# TMotor_Rev2.net
KiCad netlist of a schematic drawn in EAGLE
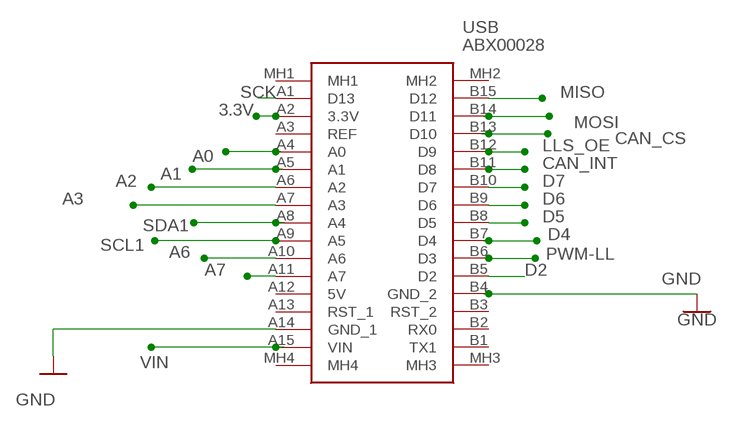
[diagram p0: schematic, sheet 1]
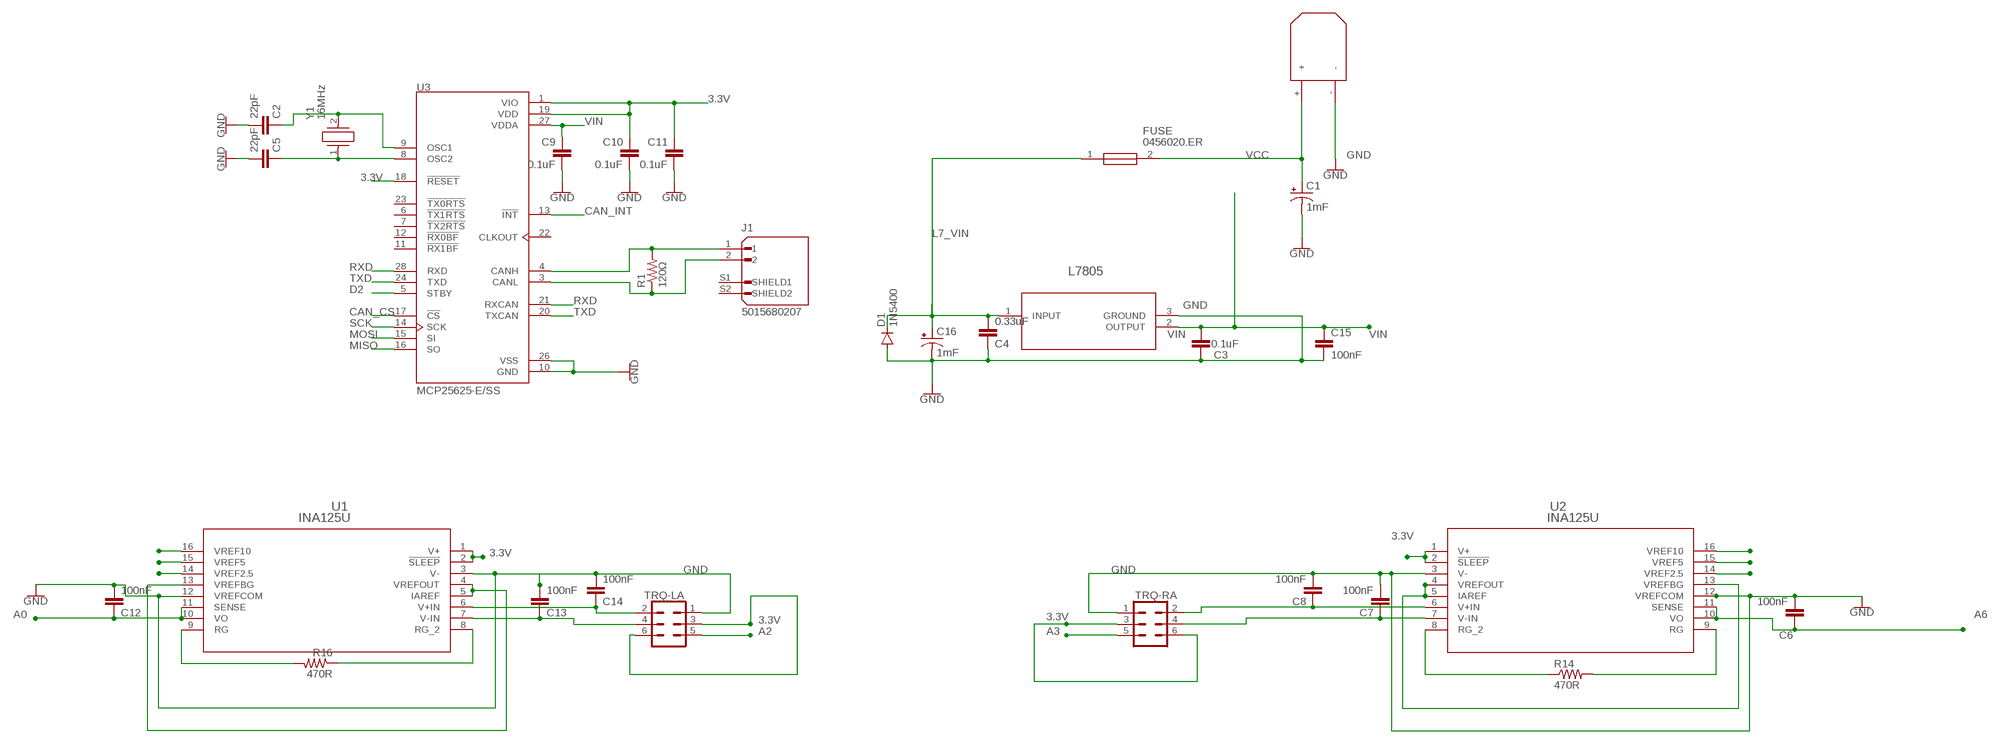
[diagram p1: schematic, sheet 2]
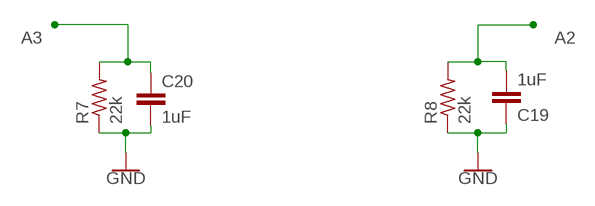
[diagram p2: schematic, sheet 3]

(export (version "E")
  (design (tool "Eeschema 10.0.6"))
  (components
    (comp (ref "C19")
      (value "1uF")
      (footprint "eagle-import:C050-024X044")
      (libsource (lib "eagle-import") (part "C-EU050-024X044"))
    )
    (comp (ref "C20")
      (value "1uF")
      (footprint "eagle-import:C050-024X044")
      (libsource (lib "eagle-import") (part "C-EU050-024X044"))
    )
    (comp (ref "R7")
      (value "22k")
      (footprint "eagle-import:0207_10")
      (libsource (lib "eagle-import") (part "resistor_348_R-US_0207/10"))
    )
    (comp (ref "R8")
      (value "22k")
      (footprint "eagle-import:0207_10")
      (libsource (lib "eagle-import") (part "resistor_348_R-US_0207/10"))
    )
    (comp (ref "USB")
      (value "ABX00028")
      (footprint "eagle-import:ABX00028")
      (fields (field (name "MOUSER_PART_NUMBER") "782-ABX00028"))
      (libsource (lib "eagle-import") (part "ABX00028"))
    )
    (comp (ref "C1")
      (value "1mF")
      (footprint "eagle-import:E5-10,5")
      (libsource (lib "eagle-import") (part "CPOL-USE5-10.5"))
    )
    (comp (ref "C2")
      (value "22pF")
      (footprint "eagle-import:C050-024X044")
      (libsource (lib "eagle-import") (part "C-EU050-024X044"))
    )
    (comp (ref "C3")
      (value "0.1uF")
      (footprint "eagle-import:C050-024X044")
      (libsource (lib "eagle-import") (part "C-EU050-024X044"))
    )
    (comp (ref "C4")
      (value "0.33uF")
      (footprint "eagle-import:C050-024X044")
      (libsource (lib "eagle-import") (part "C-EU050-024X044"))
    )
    (comp (ref "C5")
      (value "22pF")
      (footprint "eagle-import:C050-024X044")
      (libsource (lib "eagle-import") (part "C-EU050-024X044"))
    )
    (comp (ref "C6")
      (value "100nF")
      (footprint "eagle-import:C050-024X044")
      (libsource (lib "eagle-import") (part "C-EU050-024X044"))
    )
    (comp (ref "C7")
      (value "100nF")
      (footprint "eagle-import:C050-024X044")
      (libsource (lib "eagle-import") (part "C-EU050-024X044"))
    )
    (comp (ref "C8")
      (value "100nF")
      (footprint "eagle-import:C050-024X044")
      (libsource (lib "eagle-import") (part "C-EU050-024X044"))
    )
    (comp (ref "C9")
      (value "0.1uF")
      (footprint "eagle-import:C050-024X044")
      (libsource (lib "eagle-import") (part "C-EU050-024X044"))
    )
    (comp (ref "C10")
      (value "0.1uF")
      (footprint "eagle-import:C050-024X044")
      (libsource (lib "eagle-import") (part "C-EU050-024X044"))
    )
    (comp (ref "C11")
      (value "0.1uF")
      (footprint "eagle-import:C050-024X044")
      (libsource (lib "eagle-import") (part "C-EU050-024X044"))
    )
    (comp (ref "C12")
      (value "100nF")
      (footprint "eagle-import:C050-024X044")
      (libsource (lib "eagle-import") (part "C-EU050-024X044"))
    )
    (comp (ref "C13")
      (value "100nF")
      (footprint "eagle-import:C050-024X044")
      (libsource (lib "eagle-import") (part "C-EU050-024X044"))
    )
    (comp (ref "C14")
      (value "100nF")
      (footprint "eagle-import:C050-024X044")
      (libsource (lib "eagle-import") (part "C-EU050-024X044"))
    )
    (comp (ref "C15")
      (value "100nF")
      (footprint "eagle-import:C050-024X044")
      (libsource (lib "eagle-import") (part "C-EU050-024X044"))
    )
    (comp (ref "C16")
      (value "1mF")
      (footprint "eagle-import:E5-10,5")
      (libsource (lib "eagle-import") (part "CPOL-USE5-10.5"))
    )
    (comp (ref "D1")
      (value "1N5400")
      (footprint "eagle-import:DO201-15")
      (libsource (lib "eagle-import") (part "1N5400"))
    )
    (comp (ref "FUSE")
      (value "0456020.ER")
      (footprint "eagle-import:FUSC10131X312N")
      (fields (field (name "MOUSER_PART_NUMBER") "576-0456020.ER"))
      (libsource (lib "eagle-import") (part "0456020.ER"))
    )
    (comp (ref "J1")
      (value "5015680207")
      (footprint "eagle-import:MOLEX_5015680207")
      (fields (field (name "MANUFACTURER") "Molex"))
      (libsource (lib "eagle-import") (part "5015680207"))
    )
    (comp (ref "L7805")
      (value "L7805CDT-TR")
      (footprint "eagle-import:DPAK_STM")
      (libsource (lib "eagle-import") (part "L7805CDT-TR"))
    )
    (comp (ref "R1")
      (value "120Ω")
      (footprint "eagle-import:0207_10")
      (libsource (lib "eagle-import") (part "R-US_0207/10"))
    )
    (comp (ref "R14")
      (value "470R")
      (footprint "eagle-import:0207_10")
      (libsource (lib "eagle-import") (part "R-US_0207/10"))
    )
    (comp (ref "R16")
      (value "470R")
      (footprint "eagle-import:0207_10")
      (libsource (lib "eagle-import") (part "R-US_0207/10"))
    )
    (comp (ref "TRQ-LA")
      (value "CONN_03X2SHROUD")
      (footprint "eagle-import:2X3-SHROUDED")
      (libsource (lib "eagle-import") (part "CONN_03X2SHROUD"))
    )
    (comp (ref "TRQ-RA")
      (value "CONN_03X2SHROUD")
      (footprint "eagle-import:2X3-SHROUDED")
      (libsource (lib "eagle-import") (part "CONN_03X2SHROUD"))
    )
    (comp (ref "U$9")
      (value "XT30")
      (footprint "eagle-import:XT30_HORIZONTAL")
      (libsource (lib "eagle-import") (part "XT30"))
    )
    (comp (ref "U1")
      (value "INA125U")
      (footprint "eagle-import:D16")
      (fields (field (name "GENERIC_PART_NUMBER") "INA125") (field (name "MANUFACTURER") "Texas Instruments"))
      (libsource (lib "eagle-import") (part "INA125U"))
    )
    (comp (ref "U2")
      (value "INA125U")
      (footprint "eagle-import:D16")
      (fields (field (name "GENERIC_PART_NUMBER") "INA125") (field (name "MANUFACTURER") "Texas Instruments"))
      (libsource (lib "eagle-import") (part "INA125U"))
    )
    (comp (ref "U3")
      (value "MCP25625-E/SS")
      (footprint "eagle-import:SOP65P780X200-28N")
      (fields (field (name "MF") "Microchip Technology"))
      (libsource (lib "eagle-import") (part "MCP25625-E/SS"))
    )
    (comp (ref "Y1")
      (value "16MHz")
      (footprint "eagle-import:IQD-HC-49-4H")
      (fields (field (name "MANUFACTURER_PART_NUMBER") "4.91520MHz HC49/4H 30/50/-40+85C/30pF"))
      (libsource (lib "eagle-import") (part "4.91520MHZ_HC49_4H_30_50_-40+8"))
    )
  )
  (nets
    (net (code "1") (name "3.3V") (class "Default")
      (node (ref "C10") (pin "1") (pinfunction "1_1") (pintype "passive"))
      (node (ref "C11") (pin "1") (pinfunction "1_1") (pintype "passive"))
      (node (ref "TRQ-LA") (pin "3") (pinfunction "3_3") (pintype "bidirectional"))
      (node (ref "TRQ-LA") (pin "6") (pinfunction "6_6") (pintype "bidirectional"))
      (node (ref "TRQ-RA") (pin "3") (pinfunction "3_3") (pintype "bidirectional"))
      (node (ref "TRQ-RA") (pin "6") (pinfunction "6_6") (pintype "bidirectional"))
      (node (ref "U1") (pin "1") (pinfunction "V+_1") (pintype "power_in"))
      (node (ref "U1") (pin "2") (pinfunction "~{SLEEP}_2") (pintype "passive"))
      (node (ref "U2") (pin "1") (pinfunction "V+_1") (pintype "power_in"))
      (node (ref "U2") (pin "2") (pinfunction "~{SLEEP}_2") (pintype "passive"))
      (node (ref "U3") (pin "1") (pinfunction "VIO_1") (pintype "power_in"))
      (node (ref "U3") (pin "18") (pinfunction "~{RESET}_18") (pintype "input"))
      (node (ref "U3") (pin "19") (pinfunction "VDD_19") (pintype "power_in"))
      (node (ref "USB") (pin "A2") (pinfunction "3.3V_A2") (pintype "bidirectional"))
    )
    (net (code "2") (name "A0") (class "Default")
      (node (ref "C12") (pin "1") (pinfunction "1_1") (pintype "passive"))
      (node (ref "U1") (pin "10") (pinfunction "VO_10") (pintype "output"))
      (node (ref "U1") (pin "11") (pinfunction "SENSE_11") (pintype "passive"))
      (node (ref "USB") (pin "A4") (pinfunction "A0_A4") (pintype "bidirectional"))
    )
    (net (code "3") (name "A1") (class "Default")
      (node (ref "USB") (pin "A5") (pinfunction "A1_A5") (pintype "bidirectional"))
    )
    (net (code "4") (name "A2") (class "Default")
      (node (ref "C19") (pin "2") (pinfunction "2_2") (pintype "passive"))
      (node (ref "R8") (pin "2") (pinfunction "2_2") (pintype "passive"))
      (node (ref "TRQ-LA") (pin "5") (pinfunction "5_5") (pintype "bidirectional"))
      (node (ref "USB") (pin "A6") (pinfunction "A2_A6") (pintype "bidirectional"))
    )
    (net (code "5") (name "A3") (class "Default")
      (node (ref "C20") (pin "1") (pinfunction "1_1") (pintype "passive"))
      (node (ref "R7") (pin "2") (pinfunction "2_2") (pintype "passive"))
      (node (ref "TRQ-RA") (pin "5") (pinfunction "5_5") (pintype "bidirectional"))
      (node (ref "USB") (pin "A7") (pinfunction "A3_A7") (pintype "bidirectional"))
    )
    (net (code "6") (name "A6") (class "Default")
      (node (ref "C6") (pin "1") (pinfunction "1_1") (pintype "passive"))
      (node (ref "U2") (pin "10") (pinfunction "VO_10") (pintype "output"))
      (node (ref "U2") (pin "11") (pinfunction "SENSE_11") (pintype "passive"))
      (node (ref "USB") (pin "A10") (pinfunction "A6_A10") (pintype "bidirectional"))
    )
    (net (code "7") (name "A7") (class "Default")
      (node (ref "USB") (pin "A11") (pinfunction "A7_A11") (pintype "bidirectional"))
    )
    (net (code "8") (name "CAN_CS") (class "Default")
      (node (ref "U3") (pin "17") (pinfunction "~{CS}_17") (pintype "input"))
      (node (ref "USB") (pin "B13") (pinfunction "D10_B13") (pintype "bidirectional"))
    )
    (net (code "9") (name "CAN_INT") (class "Default")
      (node (ref "U3") (pin "13") (pinfunction "~{INT}_13") (pintype "output"))
      (node (ref "USB") (pin "B11") (pinfunction "D8_B11") (pintype "bidirectional"))
    )
    (net (code "10") (name "D2") (class "Default")
      (node (ref "U3") (pin "5") (pinfunction "STBY_5") (pintype "input"))
      (node (ref "USB") (pin "B5") (pinfunction "D2_B5") (pintype "bidirectional"))
    )
    (net (code "11") (name "D4") (class "Default")
      (node (ref "USB") (pin "B7") (pinfunction "D4_B7") (pintype "bidirectional"))
    )
    (net (code "12") (name "D5") (class "Default")
      (node (ref "USB") (pin "B8") (pinfunction "D5_B8") (pintype "bidirectional"))
    )
    (net (code "13") (name "D6") (class "Default")
      (node (ref "USB") (pin "B9") (pinfunction "D6_B9") (pintype "bidirectional"))
    )
    (net (code "14") (name "D7") (class "Default")
      (node (ref "USB") (pin "B10") (pinfunction "D7_B10") (pintype "bidirectional"))
    )
    (net (code "15") (name "GND") (class "Default")
      (node (ref "C1") (pin "-") (pinfunction "-_-") (pintype "passive"))
      (node (ref "C10") (pin "2") (pinfunction "2_2") (pintype "passive"))
      (node (ref "C11") (pin "2") (pinfunction "2_2") (pintype "passive"))
      (node (ref "C12") (pin "2") (pinfunction "2_2") (pintype "passive"))
      (node (ref "C13") (pin "2") (pinfunction "2_2") (pintype "passive"))
      (node (ref "C14") (pin "2") (pinfunction "2_2") (pintype "passive"))
      (node (ref "C15") (pin "2") (pinfunction "2_2") (pintype "passive"))
      (node (ref "C16") (pin "-") (pinfunction "-_-") (pintype "passive"))
      (node (ref "C19") (pin "1") (pinfunction "1_1") (pintype "passive"))
      (node (ref "C2") (pin "2") (pinfunction "2_2") (pintype "passive"))
      (node (ref "C20") (pin "2") (pinfunction "2_2") (pintype "passive"))
      (node (ref "C3") (pin "1") (pinfunction "1_1") (pintype "passive"))
      (node (ref "C4") (pin "1") (pinfunction "1_1") (pintype "passive"))
      (node (ref "C5") (pin "2") (pinfunction "2_2") (pintype "passive"))
      (node (ref "C6") (pin "2") (pinfunction "2_2") (pintype "passive"))
      (node (ref "C7") (pin "2") (pinfunction "2_2") (pintype "passive"))
      (node (ref "C8") (pin "2") (pinfunction "2_2") (pintype "passive"))
      (node (ref "C9") (pin "2") (pinfunction "2_2") (pintype "passive"))
      (node (ref "D1") (pin "A") (pinfunction "A_A") (pintype "passive"))
      (node (ref "L7805") (pin "3") (pinfunction "GROUND_3") (pintype "passive"))
      (node (ref "R7") (pin "1") (pinfunction "1_1") (pintype "passive"))
      (node (ref "R8") (pin "1") (pinfunction "1_1") (pintype "passive"))
      (node (ref "TRQ-LA") (pin "1") (pinfunction "1_1") (pintype "bidirectional"))
      (node (ref "TRQ-RA") (pin "1") (pinfunction "1_1") (pintype "bidirectional"))
      (node (ref "U$9") (pin "-") (pinfunction "-_-") (pintype "bidirectional"))
      (node (ref "U1") (pin "12") (pinfunction "VREFCOM_12") (pintype "power_in"))
      (node (ref "U1") (pin "3") (pinfunction "V-_3") (pintype "power_in"))
      (node (ref "U2") (pin "12") (pinfunction "VREFCOM_12") (pintype "power_in"))
      (node (ref "U2") (pin "3") (pinfunction "V-_3") (pintype "power_in"))
      (node (ref "U3") (pin "10") (pinfunction "GND_10") (pintype "power_in"))
      (node (ref "U3") (pin "26") (pinfunction "VSS_26") (pintype "power_in"))
      (node (ref "USB") (pin "A14") (pinfunction "GND_1_A14") (pintype "bidirectional"))
      (node (ref "USB") (pin "B4") (pinfunction "GND_2_B4") (pintype "bidirectional"))
    )
    (net (code "16") (name "L7_VIN") (class "Default")
      (node (ref "C16") (pin "+") (pinfunction "+_+") (pintype "passive"))
      (node (ref "C4") (pin "2") (pinfunction "2_2") (pintype "passive"))
      (node (ref "D1") (pin "C") (pinfunction "C_C") (pintype "passive"))
      (node (ref "FUSE") (pin "1") (pinfunction "1_1") (pintype "bidirectional"))
      (node (ref "L7805") (pin "1") (pinfunction "INPUT_1") (pintype "input"))
    )
    (net (code "17") (name "LLS_OE") (class "Default")
      (node (ref "USB") (pin "B12") (pinfunction "D9_B12") (pintype "bidirectional"))
    )
    (net (code "18") (name "MISO") (class "Default")
      (node (ref "U3") (pin "16") (pinfunction "SO_16") (pintype "output"))
      (node (ref "USB") (pin "B15") (pinfunction "D12_B15") (pintype "bidirectional"))
    )
    (net (code "19") (name "MOSI") (class "Default")
      (node (ref "U3") (pin "15") (pinfunction "SI_15") (pintype "input"))
      (node (ref "USB") (pin "B14") (pinfunction "D11_B14") (pintype "bidirectional"))
    )
    (net (code "20") (name "Net-(U1-IAREF)") (class "Default")
      (node (ref "U1") (pin "13") (pinfunction "VREFBG_13") (pintype "power_in"))
      (node (ref "U1") (pin "4") (pinfunction "VREFOUT_4") (pintype "output"))
      (node (ref "U1") (pin "5") (pinfunction "IAREF_5") (pintype "passive"))
    )
    (net (code "21") (name "Net-(U1-RG)") (class "Default")
      (node (ref "R16") (pin "2") (pinfunction "2_2") (pintype "passive"))
      (node (ref "U1") (pin "9") (pinfunction "RG_9") (pintype "passive"))
    )
    (net (code "22") (name "Net-(U1-RG_2)") (class "Default")
      (node (ref "R16") (pin "1") (pinfunction "1_1") (pintype "passive"))
      (node (ref "U1") (pin "8") (pinfunction "RG_2_8") (pintype "passive"))
    )
    (net (code "23") (name "Net-(U1-V+IN)") (class "Default")
      (node (ref "C14") (pin "1") (pinfunction "1_1") (pintype "passive"))
      (node (ref "TRQ-LA") (pin "2") (pinfunction "2_2") (pintype "bidirectional"))
      (node (ref "U1") (pin "6") (pinfunction "V+IN_6") (pintype "input"))
    )
    (net (code "24") (name "Net-(U1-V-IN)") (class "Default")
      (node (ref "C13") (pin "1") (pinfunction "1_1") (pintype "passive"))
      (node (ref "TRQ-LA") (pin "4") (pinfunction "4_4") (pintype "bidirectional"))
      (node (ref "U1") (pin "7") (pinfunction "V-IN_7") (pintype "input"))
    )
    (net (code "25") (name "Net-(U2-IAREF)") (class "Default")
      (node (ref "U2") (pin "13") (pinfunction "VREFBG_13") (pintype "power_in"))
      (node (ref "U2") (pin "4") (pinfunction "VREFOUT_4") (pintype "output"))
      (node (ref "U2") (pin "5") (pinfunction "IAREF_5") (pintype "passive"))
    )
    (net (code "26") (name "Net-(U2-RG)") (class "Default")
      (node (ref "R14") (pin "2") (pinfunction "2_2") (pintype "passive"))
      (node (ref "U2") (pin "9") (pinfunction "RG_9") (pintype "passive"))
    )
    (net (code "27") (name "Net-(U2-RG_2)") (class "Default")
      (node (ref "R14") (pin "1") (pinfunction "1_1") (pintype "passive"))
      (node (ref "U2") (pin "8") (pinfunction "RG_2_8") (pintype "passive"))
    )
    (net (code "28") (name "Net-(U2-V+IN)") (class "Default")
      (node (ref "C8") (pin "1") (pinfunction "1_1") (pintype "passive"))
      (node (ref "TRQ-RA") (pin "2") (pinfunction "2_2") (pintype "bidirectional"))
      (node (ref "U2") (pin "6") (pinfunction "V+IN_6") (pintype "input"))
    )
    (net (code "29") (name "Net-(U2-V-IN)") (class "Default")
      (node (ref "C7") (pin "1") (pinfunction "1_1") (pintype "passive"))
      (node (ref "TRQ-RA") (pin "4") (pinfunction "4_4") (pintype "bidirectional"))
      (node (ref "U2") (pin "7") (pinfunction "V-IN_7") (pintype "input"))
    )
    (net (code "30") (name "Net-(U3-CANH)") (class "Default")
      (node (ref "J1") (pin "1") (pinfunction "1_1") (pintype "passive"))
      (node (ref "R1") (pin "2") (pinfunction "2_2") (pintype "passive"))
      (node (ref "U3") (pin "4") (pinfunction "CANH_4") (pintype "bidirectional"))
    )
    (net (code "31") (name "Net-(U3-CANL)") (class "Default")
      (node (ref "J1") (pin "2") (pinfunction "2_2") (pintype "passive"))
      (node (ref "R1") (pin "1") (pinfunction "1_1") (pintype "passive"))
      (node (ref "U3") (pin "3") (pinfunction "CANL_3") (pintype "bidirectional"))
    )
    (net (code "32") (name "Net-(U3-OSC1)") (class "Default")
      (node (ref "C2") (pin "1") (pinfunction "1_1") (pintype "passive"))
      (node (ref "U3") (pin "9") (pinfunction "OSC1_9") (pintype "input"))
      (node (ref "Y1") (pin "2") (pinfunction "2_2") (pintype "bidirectional"))
    )
    (net (code "33") (name "Net-(U3-OSC2)") (class "Default")
      (node (ref "C5") (pin "1") (pinfunction "1_1") (pintype "passive"))
      (node (ref "U3") (pin "8") (pinfunction "OSC2_8") (pintype "output"))
      (node (ref "Y1") (pin "1") (pinfunction "1_1") (pintype "bidirectional"))
    )
    (net (code "34") (name "PWM-LL") (class "Default")
      (node (ref "USB") (pin "B6") (pinfunction "D3_B6") (pintype "bidirectional"))
    )
    (net (code "35") (name "RXD") (class "Default")
      (node (ref "U3") (pin "21") (pinfunction "RXCAN_21") (pintype "input"))
      (node (ref "U3") (pin "28") (pinfunction "RXD_28") (pintype "output"))
    )
    (net (code "36") (name "SCK") (class "Default")
      (node (ref "U3") (pin "14") (pinfunction "SCK_14") (pintype "input"))
      (node (ref "USB") (pin "A1") (pinfunction "D13_A1") (pintype "bidirectional"))
    )
    (net (code "37") (name "SCL1") (class "Default")
      (node (ref "USB") (pin "A9") (pinfunction "A5_A9") (pintype "bidirectional"))
    )
    (net (code "38") (name "SDA1") (class "Default")
      (node (ref "USB") (pin "A8") (pinfunction "A4_A8") (pintype "bidirectional"))
    )
    (net (code "39") (name "TXD") (class "Default")
      (node (ref "U3") (pin "20") (pinfunction "TXCAN_20") (pintype "output"))
      (node (ref "U3") (pin "24") (pinfunction "TXD_24") (pintype "input"))
    )
    (net (code "40") (name "VCC") (class "Default")
      (node (ref "C1") (pin "+") (pinfunction "+_+") (pintype "passive"))
      (node (ref "FUSE") (pin "2") (pinfunction "2_2") (pintype "bidirectional"))
      (node (ref "U$9") (pin "+") (pinfunction "+_+") (pintype "bidirectional"))
    )
    (net (code "41") (name "VIN") (class "Default")
      (node (ref "C15") (pin "1") (pinfunction "1_1") (pintype "passive"))
      (node (ref "C3") (pin "2") (pinfunction "2_2") (pintype "passive"))
      (node (ref "C9") (pin "1") (pinfunction "1_1") (pintype "passive"))
      (node (ref "L7805") (pin "2") (pinfunction "OUTPUT_2") (pintype "output"))
      (node (ref "U3") (pin "27") (pinfunction "VDDA_27") (pintype "power_in"))
      (node (ref "USB") (pin "A15") (pinfunction "VIN_A15") (pintype "bidirectional"))
    )
    (net (code "42") (name "unconnected-(J1-SHIELD1-PadS1)") (class "Default")
      (node (ref "J1") (pin "S1") (pinfunction "SHIELD1_S1") (pintype "passive"))
    )
    (net (code "43") (name "unconnected-(J1-SHIELD2-PadS2)") (class "Default")
      (node (ref "J1") (pin "S2") (pinfunction "SHIELD2_S2") (pintype "passive"))
    )
    (net (code "44") (name "unconnected-(U1-VREF2.5-Pad14)") (class "Default")
      (node (ref "U1") (pin "14") (pinfunction "VREF2.5_14") (pintype "power_in"))
    )
    (net (code "45") (name "unconnected-(U1-VREF5-Pad15)") (class "Default")
      (node (ref "U1") (pin "15") (pinfunction "VREF5_15") (pintype "power_in"))
    )
    (net (code "46") (name "unconnected-(U1-VREF10-Pad16)") (class "Default")
      (node (ref "U1") (pin "16") (pinfunction "VREF10_16") (pintype "power_in"))
    )
    (net (code "47") (name "unconnected-(U2-VREF2.5-Pad14)") (class "Default")
      (node (ref "U2") (pin "14") (pinfunction "VREF2.5_14") (pintype "power_in"))
    )
    (net (code "48") (name "unconnected-(U2-VREF5-Pad15)") (class "Default")
      (node (ref "U2") (pin "15") (pinfunction "VREF5_15") (pintype "power_in"))
    )
    (net (code "49") (name "unconnected-(U2-VREF10-Pad16)") (class "Default")
      (node (ref "U2") (pin "16") (pinfunction "VREF10_16") (pintype "power_in"))
    )
    (net (code "50") (name "unconnected-(U3-CLKOUT-Pad22)") (class "Default")
      (node (ref "U3") (pin "22") (pinfunction "CLKOUT_22") (pintype "output"))
    )
    (net (code "51") (name "unconnected-(U3-~{RX0BF}-Pad12)") (class "Default")
      (node (ref "U3") (pin "12") (pinfunction "~{RX0BF}_12") (pintype "output"))
    )
    (net (code "52") (name "unconnected-(U3-~{RX1BF}-Pad11)") (class "Default")
      (node (ref "U3") (pin "11") (pinfunction "~{RX1BF}_11") (pintype "output"))
    )
    (net (code "53") (name "unconnected-(U3-~{TX0RTS}-Pad23)") (class "Default")
      (node (ref "U3") (pin "23") (pinfunction "~{TX0RTS}_23") (pintype "input"))
    )
    (net (code "54") (name "unconnected-(U3-~{TX1RTS}-Pad6)") (class "Default")
      (node (ref "U3") (pin "6") (pinfunction "~{TX1RTS}_6") (pintype "input"))
    )
    (net (code "55") (name "unconnected-(U3-~{TX2RTS}-Pad7)") (class "Default")
      (node (ref "U3") (pin "7") (pinfunction "~{TX2RTS}_7") (pintype "input"))
    )
    (net (code "56") (name "unconnected-(USB-5V-PadA12)") (class "Default")
      (node (ref "USB") (pin "A12") (pinfunction "5V_A12") (pintype "bidirectional"))
    )
    (net (code "57") (name "unconnected-(USB-PadMH1)") (class "Default")
      (node (ref "USB") (pin "MH1") (pinfunction "MH1_MH1") (pintype "bidirectional"))
    )
    (net (code "58") (name "unconnected-(USB-PadMH2)") (class "Default")
      (node (ref "USB") (pin "MH2") (pinfunction "MH2_MH2") (pintype "bidirectional"))
    )
    (net (code "59") (name "unconnected-(USB-PadMH3)") (class "Default")
      (node (ref "USB") (pin "MH3") (pinfunction "MH3_MH3") (pintype "bidirectional"))
    )
    (net (code "60") (name "unconnected-(USB-PadMH4)") (class "Default")
      (node (ref "USB") (pin "MH4") (pinfunction "MH4_MH4") (pintype "bidirectional"))
    )
    (net (code "61") (name "unconnected-(USB-REF-PadA3)") (class "Default")
      (node (ref "USB") (pin "A3") (pinfunction "REF_A3") (pintype "bidirectional"))
    )
    (net (code "62") (name "unconnected-(USB-RST_1-PadA13)") (class "Default")
      (node (ref "USB") (pin "A13") (pinfunction "RST_1_A13") (pintype "bidirectional"))
    )
    (net (code "63") (name "unconnected-(USB-RST_2-PadB3)") (class "Default")
      (node (ref "USB") (pin "B3") (pinfunction "RST_2_B3") (pintype "bidirectional"))
    )
    (net (code "64") (name "unconnected-(USB-RX0-PadB2)") (class "Default")
      (node (ref "USB") (pin "B2") (pinfunction "RX0_B2") (pintype "bidirectional"))
    )
    (net (code "65") (name "unconnected-(USB-TX1-PadB1)") (class "Default")
      (node (ref "USB") (pin "B1") (pinfunction "TX1_B1") (pintype "bidirectional"))
    )
  )
)
